# controller_board.net
KiCad netlist of a schematic drawn in EAGLE
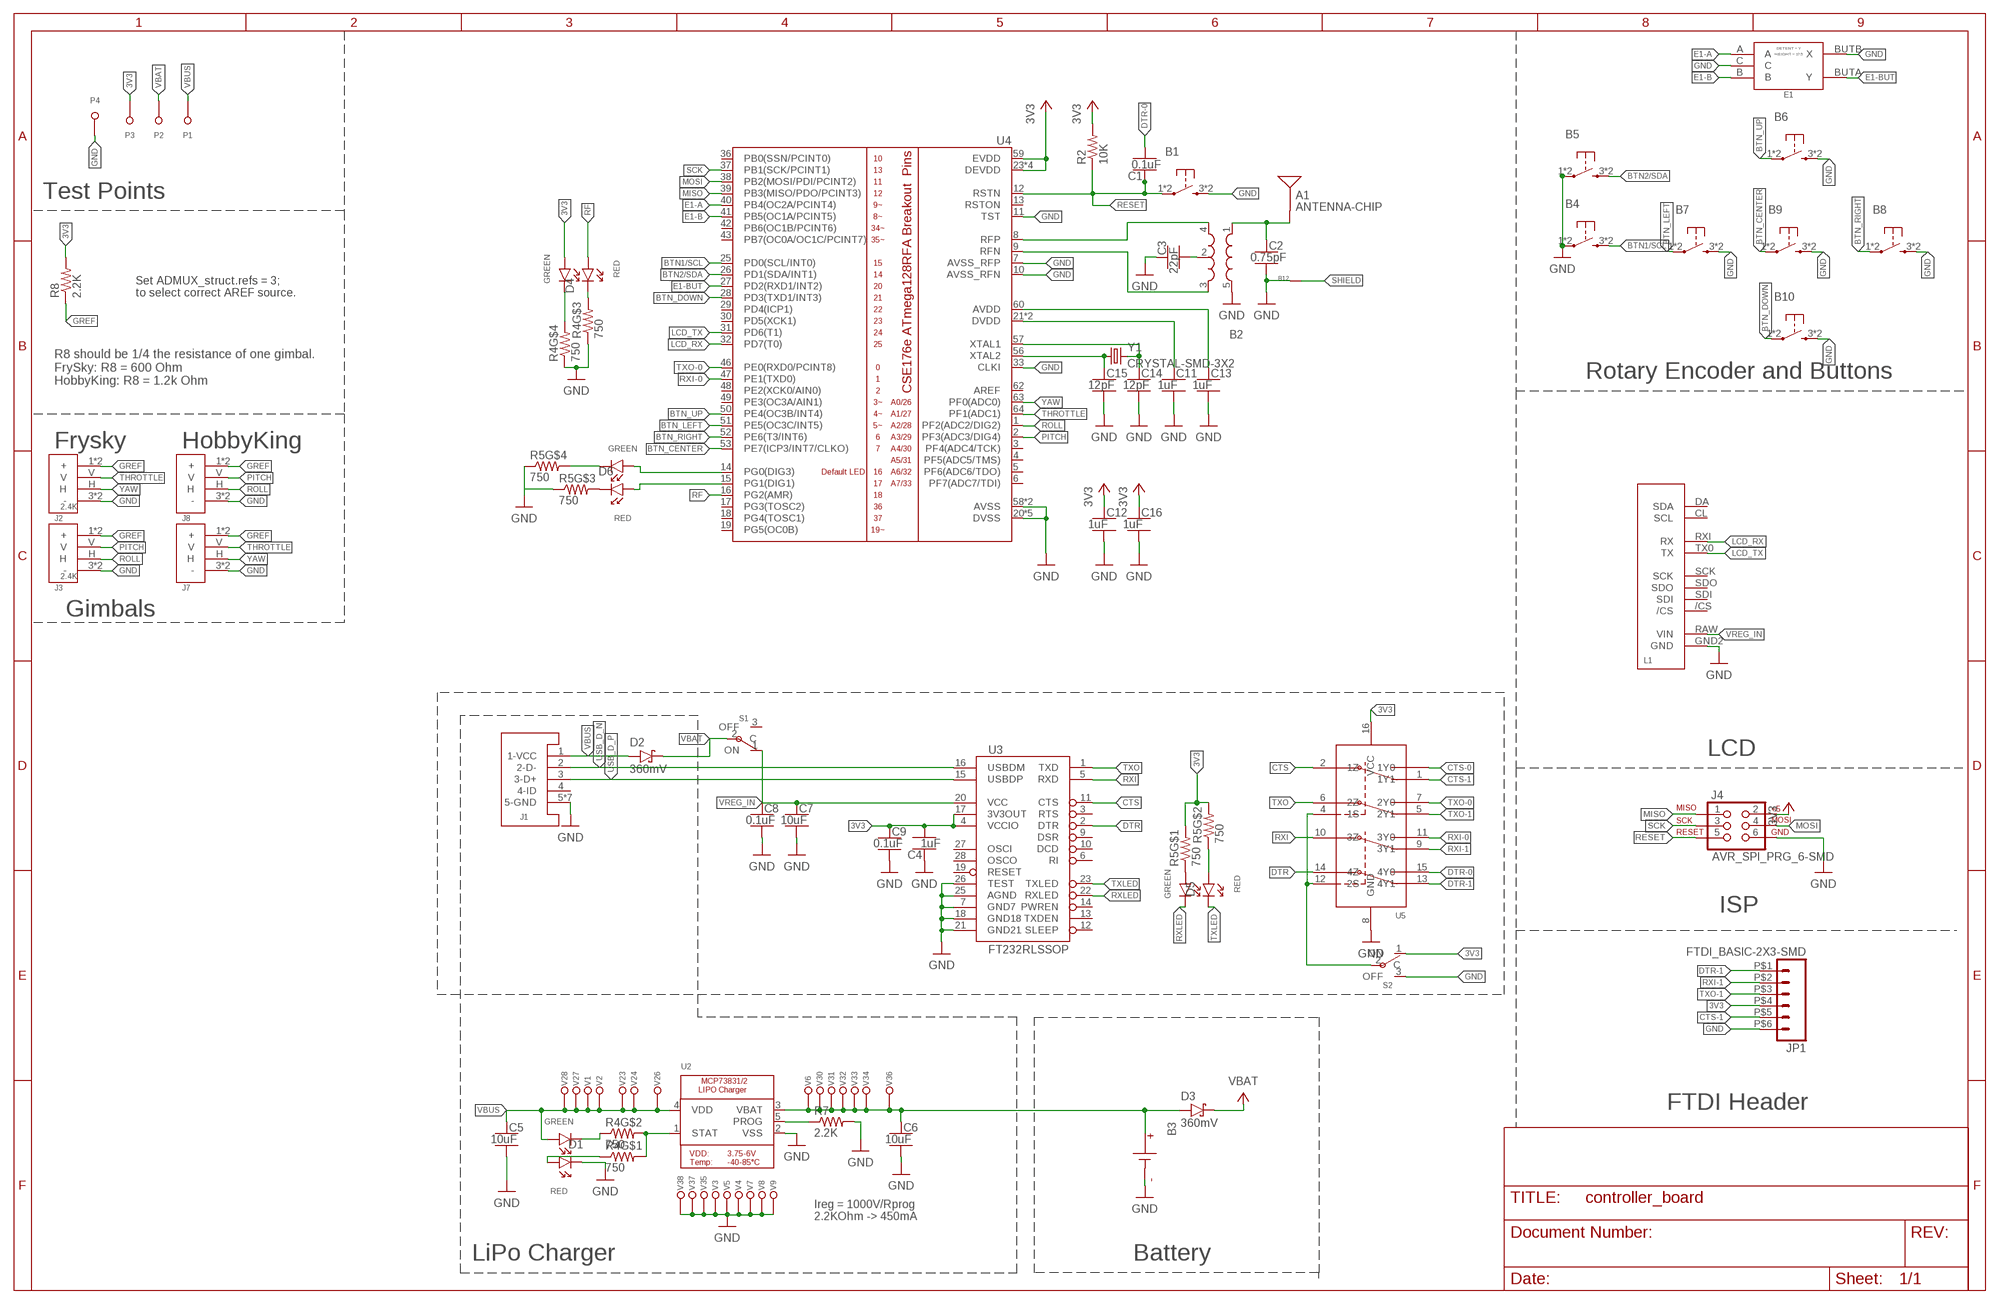
[diagram p0: schematic, sheet 1]

(export (version "E")
  (design (tool "Eeschema 10.0.6"))
  (components
    (comp (ref "A1")
      (value "ANTENNA-CHIP")
      (footprint "eagle-import:ANTENNA-CHIP")
      (fields
        (field (name "MFR") "Linx Technologies Inc.")
        (field (name "MPN") "ANT-2.45-CHP-T")
        (field (name "CREATOR") "Swanson")
        (field (name "REVIEWER") "Swanson")
      )
      (libsource (lib "eagle-import") (part "ANTENNA-CHIP"))
    )
    (comp (ref "B1")
      (value "PUSHBUTTON_-4.5X4.5")
      (footprint "eagle-import:4.5MM_TACTILE_SWITCH_TL3305AF160QG")
      (fields (field (name "CREATOR") "Swanson"))
      (libsource (lib "eagle-import") (part "PUSHBUTTON_-4.5X4.5"))
    )
    (comp (ref "B2")
      (value "BALUN0805")
      (footprint "eagle-import:BALUN")
      (fields
        (field (name "MFR") "Wurth Electronics Inc")
        (field (name "MPN") "748421245")
        (field (name "CREATOR") "Swanson")
        (field (name "REVIEWER") "Swanson")
      )
      (libsource (lib "eagle-import") (part "BALUN0805"))
    )
    (comp (ref "B3")
      (value "BATTERY-SMD")
      (footprint "eagle-import:MOLEX-BATTERY-CONNECTOR-SMD-51005-2P")
      (libsource (lib "eagle-import") (part "BATTERY-SMD"))
    )
    (comp (ref "B4")
      (value "PUSHBUTTON_-4.5X4.5")
      (footprint "eagle-import:4.5MM_TACTILE_SWITCH_TL3305AF160QG")
      (fields (field (name "CREATOR") "Swanson"))
      (libsource (lib "eagle-import") (part "PUSHBUTTON_-4.5X4.5"))
    )
    (comp (ref "B5")
      (value "PUSHBUTTON_-4.5X4.5")
      (footprint "eagle-import:4.5MM_TACTILE_SWITCH_TL3305AF160QG")
      (fields (field (name "CREATOR") "Swanson"))
      (libsource (lib "eagle-import") (part "PUSHBUTTON_-4.5X4.5"))
    )
    (comp (ref "B6")
      (value "PUSHBUTTON_-4.5X4.5")
      (footprint "eagle-import:4.5MM_TACTILE_SWITCH_TL3305AF160QG")
      (fields (field (name "CREATOR") "Swanson"))
      (libsource (lib "eagle-import") (part "PUSHBUTTON_-4.5X4.5"))
    )
    (comp (ref "B7")
      (value "PUSHBUTTON_-4.5X4.5")
      (footprint "eagle-import:4.5MM_TACTILE_SWITCH_TL3305AF160QG")
      (fields (field (name "CREATOR") "Swanson"))
      (libsource (lib "eagle-import") (part "PUSHBUTTON_-4.5X4.5"))
    )
    (comp (ref "B8")
      (value "PUSHBUTTON_-4.5X4.5")
      (footprint "eagle-import:4.5MM_TACTILE_SWITCH_TL3305AF160QG")
      (fields (field (name "CREATOR") "Swanson"))
      (libsource (lib "eagle-import") (part "PUSHBUTTON_-4.5X4.5"))
    )
    (comp (ref "B9")
      (value "PUSHBUTTON_-4.5X4.5")
      (footprint "eagle-import:4.5MM_TACTILE_SWITCH_TL3305AF160QG")
      (fields (field (name "CREATOR") "Swanson"))
      (libsource (lib "eagle-import") (part "PUSHBUTTON_-4.5X4.5"))
    )
    (comp (ref "B10")
      (value "PUSHBUTTON_-4.5X4.5")
      (footprint "eagle-import:4.5MM_TACTILE_SWITCH_TL3305AF160QG")
      (fields (field (name "CREATOR") "Swanson"))
      (libsource (lib "eagle-import") (part "PUSHBUTTON_-4.5X4.5"))
    )
    (comp (ref "B12")
      (value "NET_BRIDGE")
      (footprint "eagle-import:NET_BRIDGE")
      (fields (field (name "CREATOR") "Michael Gonzalez"))
      (libsource (lib "eagle-import") (part "NET_BRIDGE"))
    )
    (comp (ref "C1")
      (value "0.1uF")
      (footprint "eagle-import:CAPC1608X100")
      (fields (field (name "CREATOR") "Swanson"))
      (libsource (lib "eagle-import") (part "CAPACITOR-NP_SMD-0603_CERAMIC-0.1UF"))
    )
    (comp (ref "C2")
      (value "0.75pF")
      (footprint "eagle-import:CAPC1608X100")
      (fields (field (name "CREATOR") "Swanson"))
      (libsource (lib "eagle-import") (part "CAPACITOR-NP_SMD-0603_CERAMIC-0.75PF"))
    )
    (comp (ref "C3")
      (value "22pF")
      (footprint "eagle-import:CAPC1608X100")
      (fields (field (name "CREATOR") "Swanson"))
      (libsource (lib "eagle-import") (part "CAPACITOR-NP_SMD-0603_CERAMIC-22PF"))
    )
    (comp (ref "C4")
      (value "1uF")
      (footprint "eagle-import:CAPC1608X100")
      (fields (field (name "CREATOR") "Swanson"))
      (libsource (lib "eagle-import") (part "CAPACITOR-NP_SMD-0603_CERAMIC-1UF"))
    )
    (comp (ref "C5")
      (value "10uF")
      (footprint "eagle-import:CAPC1608X100")
      (fields (field (name "CREATOR") "Swanson"))
      (libsource (lib "eagle-import") (part "CAPACITOR-NP_SMD-0603_CERAMIC-10UF"))
    )
    (comp (ref "C6")
      (value "10uF")
      (footprint "eagle-import:CAPC1608X100")
      (fields (field (name "CREATOR") "Swanson"))
      (libsource (lib "eagle-import") (part "CAPACITOR-NP_SMD-0603_CERAMIC-10UF"))
    )
    (comp (ref "C7")
      (value "10uF")
      (footprint "eagle-import:CAPC1608X100")
      (fields (field (name "CREATOR") "Swanson"))
      (libsource (lib "eagle-import") (part "CAPACITOR-NP_SMD-0603_CERAMIC-10UF"))
    )
    (comp (ref "C8")
      (value "0.1uF")
      (footprint "eagle-import:CAPC1608X100")
      (fields (field (name "CREATOR") "Swanson"))
      (libsource (lib "eagle-import") (part "CAPACITOR-NP_SMD-0603_CERAMIC-0.1UF"))
    )
    (comp (ref "C9")
      (value "0.1uF")
      (footprint "eagle-import:CAPC1608X100")
      (fields (field (name "CREATOR") "Swanson"))
      (libsource (lib "eagle-import") (part "CAPACITOR-NP_SMD-0603_CERAMIC-0.1UF"))
    )
    (comp (ref "C11")
      (value "1uF")
      (footprint "eagle-import:CAPC1608X100")
      (fields (field (name "CREATOR") "Swanson"))
      (libsource (lib "eagle-import") (part "CAPACITOR-NP_SMD-0603_CERAMIC-1UF"))
    )
    (comp (ref "C12")
      (value "1uF")
      (footprint "eagle-import:CAPC1608X100")
      (fields (field (name "CREATOR") "Swanson"))
      (libsource (lib "eagle-import") (part "CAPACITOR-NP_SMD-0603_CERAMIC-1UF"))
    )
    (comp (ref "C13")
      (value "1uF")
      (footprint "eagle-import:CAPC1608X100")
      (fields (field (name "CREATOR") "Swanson"))
      (libsource (lib "eagle-import") (part "CAPACITOR-NP_SMD-0603_CERAMIC-1UF"))
    )
    (comp (ref "C14")
      (value "12pF")
      (footprint "eagle-import:CAPC1608X100")
      (fields (field (name "CREATOR") "Swanson"))
      (libsource (lib "eagle-import") (part "CAPACITOR-NP_SMD-0603_CERAMIC-12PF"))
    )
    (comp (ref "C15")
      (value "12pF")
      (footprint "eagle-import:CAPC1608X100")
      (fields (field (name "CREATOR") "Swanson"))
      (libsource (lib "eagle-import") (part "CAPACITOR-NP_SMD-0603_CERAMIC-12PF"))
    )
    (comp (ref "C16")
      (value "1uF")
      (footprint "eagle-import:CAPC1608X100")
      (fields (field (name "CREATOR") "Swanson"))
      (libsource (lib "eagle-import") (part "CAPACITOR-NP_SMD-0603_CERAMIC-1UF"))
    )
    (comp (ref "D1")
      (value "LED-2X-GREEN/RED-1.6X1.5MM")
      (footprint "eagle-import:LED-2X-LITE-ON-1.6MMX1.5MM")
      (fields
        (field (name "COLOR2") "RED")
        (field (name "COLOR1") "GREEN")
        (field (name "CREATOR") "Swanson")
      )
      (libsource (lib "eagle-import") (part "LED-2X-GREEN/RED-1.6X1.5MM"))
    )
    (comp (ref "D2")
      (value "360mV")
      (footprint "eagle-import:SOD3716X135_HS")
      (fields
        (field (name "MFR") "Toshiba Semiconductor and Storage")
        (field (name "MPN") "CRS08(TE85L,Q,M)")
        (field (name "CREATOR") "Swanson")
        (field (name "REVIEWER") "Swanson")
      )
      (libsource (lib "eagle-import") (part "DIODE-SCHOTTKY_SMD-SOD123-360MV"))
    )
    (comp (ref "D3")
      (value "360mV")
      (footprint "eagle-import:SOD3716X135_HS")
      (fields
        (field (name "MFR") "Toshiba Semiconductor and Storage")
        (field (name "MPN") "CRS08(TE85L,Q,M)")
        (field (name "CREATOR") "Swanson")
        (field (name "REVIEWER") "Swanson")
      )
      (libsource (lib "eagle-import") (part "DIODE-SCHOTTKY_SMD-SOD123-360MV"))
    )
    (comp (ref "D4")
      (value "LED-2X-GREEN/RED-1.6X1.5MM")
      (footprint "eagle-import:LED-2X-LITE-ON-1.6MMX1.5MM")
      (fields
        (field (name "COLOR2") "RED")
        (field (name "COLOR1") "GREEN")
        (field (name "CREATOR") "Swanson")
      )
      (libsource (lib "eagle-import") (part "LED-2X-GREEN/RED-1.6X1.5MM"))
    )
    (comp (ref "D5")
      (value "LED-2X-GREEN/RED-1.6X1.5MM")
      (footprint "eagle-import:LED-2X-LITE-ON-1.6MMX1.5MM")
      (fields
        (field (name "COLOR2") "RED")
        (field (name "COLOR1") "GREEN")
        (field (name "CREATOR") "Swanson")
      )
      (libsource (lib "eagle-import") (part "LED-2X-GREEN/RED-1.6X1.5MM"))
    )
    (comp (ref "D6")
      (value "LED-2X-GREEN/RED-1.6X1.5MM")
      (footprint "eagle-import:LED-2X-LITE-ON-1.6MMX1.5MM")
      (fields
        (field (name "COLOR2") "RED")
        (field (name "COLOR1") "GREEN")
        (field (name "CREATOR") "Swanson")
      )
      (libsource (lib "eagle-import") (part "LED-2X-GREEN/RED-1.6X1.5MM"))
    )
    (comp (ref "E1")
      (value "ROTARY-ENCODER-W/BUTTON-BOURNS-PEC12R-4217F")
      (footprint "eagle-import:BOURNS-PEC12R")
      (fields (field (name "DETENT") "Y") (field (name "HEIGHT") "17.5") (field (name "CREATOR") "Swanson"))
      (libsource (lib "eagle-import") (part "ROTARY-ENCODER-W/BUTTON-BOURNS-PEC12R-4217F"))
    )
    (comp (ref "J1")
      (value "USB-MICROA-AMPHENOL-10118192-0001LF")
      (footprint "eagle-import:USB-MICROA-10118192-0001LF")
      (fields (field (name "CREATOR") "Swanson"))
      (libsource (lib "eagle-import") (part "USB-MICROA-AMPHENOL-10118192-0001LF"))
    )
    (comp (ref "J2")
      (value "2.4K")
      (footprint "eagle-import:JST-13-PTH")
      (fields (field (name "CREATOR") "Swanson"))
      (libsource (lib "eagle-import") (part "FRSKY-GIMBAL-FRYSKY"))
    )
    (comp (ref "J3")
      (value "2.4K")
      (footprint "eagle-import:JST-13-PTH")
      (fields (field (name "SPICEPREFIX") "E") (field (name "CREATOR") "Swanson"))
      (libsource (lib "eagle-import") (part "FRSKY-GIMBAL-FRYSKY"))
    )
    (comp (ref "J4")
      (value "AVR_SPI_PRG_6-SMD")
      (footprint "eagle-import:2X3-SMD")
      (fields (field (name "CREATOR") "Swanson"))
      (libsource (lib "eagle-import") (part "AVR_SPI_PRG_6-SMD"))
    )
    (comp (ref "J7")
      (value "FRSKY-GIMBAL-2X-SERVO-SMD")
      (footprint "eagle-import:2X-SERVO-SMD")
      (libsource (lib "eagle-import") (part "FRSKY-GIMBAL-2X-SERVO-SMD"))
    )
    (comp (ref "J8")
      (value "FRSKY-GIMBAL-2X-SERVO-SMD")
      (footprint "eagle-import:2X-SERVO-SMD")
      (libsource (lib "eagle-import") (part "FRSKY-GIMBAL-2X-SERVO-SMD"))
    )
    (comp (ref "JP1")
      (value "FTDI_BASIC-2X3-SMD")
      (footprint "eagle-import:FTDI-2X3-SMD")
      (libsource (lib "eagle-import") (part "FTDI_BASIC-2X3-SMD"))
    )
    (comp (ref "L1")
      (value "SPARKFUN_SERLCD_SERIAL_REDUCED-SMD")
      (footprint "eagle-import:SPARKFUN_SERLCD_16X2_REDUCED_SMD")
      (fields (field (name "CREATOR") "Swanson"))
      (libsource (lib "eagle-import") (part "SPARKFUN_SERLCD_SERIAL_REDUCED-SMD"))
    )
    (comp (ref "P1")
      (value "TEST-POINT")
      (footprint "eagle-import:TEST-POINT-KEYSTONE-5000")
      (fields (field (name "CREATOR") "Swanson"))
      (libsource (lib "eagle-import") (part "TEST-POINT"))
    )
    (comp (ref "P2")
      (value "TEST-POINT")
      (footprint "eagle-import:TEST-POINT-KEYSTONE-5000")
      (fields (field (name "CREATOR") "Swanson"))
      (libsource (lib "eagle-import") (part "TEST-POINT"))
    )
    (comp (ref "P3")
      (value "TEST-POINT")
      (footprint "eagle-import:TEST-POINT-KEYSTONE-5000")
      (fields (field (name "CREATOR") "Swanson"))
      (libsource (lib "eagle-import") (part "TEST-POINT"))
    )
    (comp (ref "P4")
      (value "TEST-POINT")
      (footprint "eagle-import:TEST-POINT-KEYSTONE-5000")
      (fields (field (name "CREATOR") "Swanson"))
      (libsource (lib "eagle-import") (part "TEST-POINT"))
    )
    (comp (ref "R2")
      (value "10K")
      (footprint "eagle-import:RESC1608X55")
      (fields (field (name "CREATOR") "Swanson"))
      (libsource (lib "eagle-import") (part "RESISTOR_SMD-0603-10K"))
    )
    (comp (ref "R4")
      (value "750")
      (footprint "eagle-import:RESCAXS50P200X100X45-8")
      (fields (field (name "CREATOR") "Swanson"))
      (libsource (lib "eagle-import") (part "RESISTOR-PACK-4X-750"))
    )
    (comp (ref "R5")
      (value "750")
      (footprint "eagle-import:RESCAXS50P200X100X45-8")
      (fields (field (name "CREATOR") "Swanson"))
      (libsource (lib "eagle-import") (part "RESISTOR-PACK-4X-750"))
    )
    (comp (ref "R7")
      (value "2.2K")
      (footprint "eagle-import:RESC1608X55")
      (fields (field (name "CREATOR") "Swanson"))
      (libsource (lib "eagle-import") (part "RESISTOR_SMD-0603-2.2K"))
    )
    (comp (ref "R8")
      (value "2.2K")
      (footprint "eagle-import:RESC1608X55")
      (fields (field (name "CREATOR") "Swanson"))
      (libsource (lib "eagle-import") (part "RESISTOR_SMD-0603-2.2K"))
    )
    (comp (ref "S1")
      (value "POWER-SWITCH-MFS201N-9-Z-SMD-VERTICAL")
      (footprint "eagle-import:JS102011JCQN")
      (fields (field (name "CREATOR") "Swanson"))
      (libsource (lib "eagle-import") (part "POWER-SWITCH-MFS201N-9-Z-SMD-VERTICAL"))
    )
    (comp (ref "S2")
      (value "POWER-SWITCH-MFS201N-9-Z-SMD-VERTICAL")
      (footprint "eagle-import:JS102011JCQN")
      (fields (field (name "CREATOR") "Swanson"))
      (libsource (lib "eagle-import") (part "POWER-SWITCH-MFS201N-9-Z-SMD-VERTICAL"))
    )
    (comp (ref "U2")
      (value "MCP73831T-2ACI/OT")
      (footprint "eagle-import:SOT23-5")
      (fields (field (name "CREATOR") "Adafruit"))
      (libsource (lib "eagle-import") (part "MCP73831/2"))
    )
    (comp (ref "U3")
      (value "FT232RLSSOP")
      (footprint "eagle-import:SSOP28DB")
      (fields (field (name "CREATOR") "Swanson"))
      (libsource (lib "eagle-import") (part "FT232RLSSOP"))
    )
    (comp (ref "U4")
      (value "ATMEGA128RFA1")
      (footprint "eagle-import:QFN-64")
      (fields
        (field (name "MFR") "Atmel")
        (field (name "MPN") "ATMEGA128RFA1-ZUR00")
        (field (name "CREATOR") "Swanson")
        (field (name "REVIEWER") "Swanson")
      )
      (libsource (lib "eagle-import") (part "ATMEGA128RFA1"))
    )
    (comp (ref "U5")
      (value "DPDT-X2")
      (footprint "eagle-import:SOP65P640X110-16")
      (fields (field (name "CREATOR") "Swanson"))
      (libsource (lib "eagle-import") (part "DPDT-X2"))
    )
    (comp (ref "V1")
      (value "LOCKED-VIA-0.2")
      (footprint "eagle-import:VIA-0.2MM")
      (fields (field (name "CREATOR") "Swanson"))
      (libsource (lib "eagle-import") (part "LOCKED-VIA-0.2"))
    )
    (comp (ref "V2")
      (value "LOCKED-VIA-0.2")
      (footprint "eagle-import:VIA-0.2MM")
      (fields (field (name "CREATOR") "Swanson"))
      (libsource (lib "eagle-import") (part "LOCKED-VIA-0.2"))
    )
    (comp (ref "V3")
      (value "LOCKED-VIA-0.2")
      (footprint "eagle-import:VIA-0.2MM")
      (fields (field (name "CREATOR") "Swanson"))
      (libsource (lib "eagle-import") (part "LOCKED-VIA-0.2"))
    )
    (comp (ref "V4")
      (value "LOCKED-VIA-0.2")
      (footprint "eagle-import:VIA-0.2MM")
      (fields (field (name "CREATOR") "Swanson"))
      (libsource (lib "eagle-import") (part "LOCKED-VIA-0.2"))
    )
    (comp (ref "V5")
      (value "LOCKED-VIA-0.2")
      (footprint "eagle-import:VIA-0.2MM")
      (fields (field (name "CREATOR") "Swanson"))
      (libsource (lib "eagle-import") (part "LOCKED-VIA-0.2"))
    )
    (comp (ref "V6")
      (value "LOCKED-VIA-0.2")
      (footprint "eagle-import:VIA-0.2MM")
      (fields (field (name "CREATOR") "Swanson"))
      (libsource (lib "eagle-import") (part "LOCKED-VIA-0.2"))
    )
    (comp (ref "V7")
      (value "LOCKED-VIA-0.2")
      (footprint "eagle-import:VIA-0.2MM")
      (fields (field (name "CREATOR") "Swanson"))
      (libsource (lib "eagle-import") (part "LOCKED-VIA-0.2"))
    )
    (comp (ref "V8")
      (value "LOCKED-VIA-0.2")
      (footprint "eagle-import:VIA-0.2MM")
      (fields (field (name "CREATOR") "Swanson"))
      (libsource (lib "eagle-import") (part "LOCKED-VIA-0.2"))
    )
    (comp (ref "V9")
      (value "LOCKED-VIA-0.2")
      (footprint "eagle-import:VIA-0.2MM")
      (fields (field (name "CREATOR") "Swanson"))
      (libsource (lib "eagle-import") (part "LOCKED-VIA-0.2"))
    )
    (comp (ref "V23")
      (value "LOCKED-VIA-0.2")
      (footprint "eagle-import:VIA-0.2MM")
      (fields (field (name "CREATOR") "Swanson"))
      (libsource (lib "eagle-import") (part "LOCKED-VIA-0.2"))
    )
    (comp (ref "V24")
      (value "LOCKED-VIA-0.2")
      (footprint "eagle-import:VIA-0.2MM")
      (fields (field (name "CREATOR") "Swanson"))
      (libsource (lib "eagle-import") (part "LOCKED-VIA-0.2"))
    )
    (comp (ref "V26")
      (value "LOCKED-VIA-0.2")
      (footprint "eagle-import:VIA-0.2MM")
      (fields (field (name "CREATOR") "Swanson"))
      (libsource (lib "eagle-import") (part "LOCKED-VIA-0.2"))
    )
    (comp (ref "V27")
      (value "LOCKED-VIA-0.2")
      (footprint "eagle-import:VIA-0.2MM")
      (fields (field (name "CREATOR") "Swanson"))
      (libsource (lib "eagle-import") (part "LOCKED-VIA-0.2"))
    )
    (comp (ref "V28")
      (value "LOCKED-VIA-0.2")
      (footprint "eagle-import:VIA-0.2MM")
      (fields (field (name "CREATOR") "Swanson"))
      (libsource (lib "eagle-import") (part "LOCKED-VIA-0.2"))
    )
    (comp (ref "V30")
      (value "LOCKED-VIA-0.2")
      (footprint "eagle-import:VIA-0.2MM")
      (fields (field (name "CREATOR") "Swanson"))
      (libsource (lib "eagle-import") (part "LOCKED-VIA-0.2"))
    )
    (comp (ref "V31")
      (value "LOCKED-VIA-0.2")
      (footprint "eagle-import:VIA-0.2MM")
      (fields (field (name "CREATOR") "Swanson"))
      (libsource (lib "eagle-import") (part "LOCKED-VIA-0.2"))
    )
    (comp (ref "V32")
      (value "LOCKED-VIA-0.2")
      (footprint "eagle-import:VIA-0.2MM")
      (fields (field (name "CREATOR") "Swanson"))
      (libsource (lib "eagle-import") (part "LOCKED-VIA-0.2"))
    )
    (comp (ref "V33")
      (value "LOCKED-VIA-0.2")
      (footprint "eagle-import:VIA-0.2MM")
      (fields (field (name "CREATOR") "Swanson"))
      (libsource (lib "eagle-import") (part "LOCKED-VIA-0.2"))
    )
    (comp (ref "V34")
      (value "LOCKED-VIA-0.2")
      (footprint "eagle-import:VIA-0.2MM")
      (fields (field (name "CREATOR") "Swanson"))
      (libsource (lib "eagle-import") (part "LOCKED-VIA-0.2"))
    )
    (comp (ref "V35")
      (value "LOCKED-VIA-0.2")
      (footprint "eagle-import:VIA-0.2MM")
      (fields (field (name "CREATOR") "Swanson"))
      (libsource (lib "eagle-import") (part "LOCKED-VIA-0.2"))
    )
    (comp (ref "V36")
      (value "LOCKED-VIA-0.2")
      (footprint "eagle-import:VIA-0.2MM")
      (fields (field (name "CREATOR") "Swanson"))
      (libsource (lib "eagle-import") (part "LOCKED-VIA-0.2"))
    )
    (comp (ref "V37")
      (value "LOCKED-VIA-0.2")
      (footprint "eagle-import:VIA-0.2MM")
      (fields (field (name "CREATOR") "Swanson"))
      (libsource (lib "eagle-import") (part "LOCKED-VIA-0.2"))
    )
    (comp (ref "V38")
      (value "LOCKED-VIA-0.2")
      (footprint "eagle-import:VIA-0.2MM")
      (fields (field (name "CREATOR") "Swanson"))
      (libsource (lib "eagle-import") (part "LOCKED-VIA-0.2"))
    )
    (comp (ref "Y1")
      (value "CRYSTAL-SMD-3X2")
      (footprint "eagle-import:OSCCC320X250X85")
      (fields (field (name "CREATOR") "Swanson"))
      (libsource (lib "eagle-import") (part "CRYSTAL-SMD-3X2"))
    )
  )
  (nets
    (net (code "1") (name "3V3") (class "Default")
      (node (ref "C12") (pin "1") (pinfunction "1_1") (pintype "passive"))
      (node (ref "C16") (pin "1") (pinfunction "1_1") (pintype "passive"))
      (node (ref "C4") (pin "2") (pinfunction "2_2") (pintype "passive"))
      (node (ref "C9") (pin "1") (pinfunction "1_1") (pintype "passive"))
      (node (ref "D4") (pin "A2") (pinfunction "A2_A2") (pintype "passive"))
      (node (ref "J4") (pin "2") (pinfunction "2_2") (pintype "passive"))
      (node (ref "JP1") (pin "P$4") (pinfunction "4_P$4") (pintype "passive"))
      (node (ref "P3") (pin "T") (pinfunction "T_T") (pintype "bidirectional"))
      (node (ref "R2") (pin "2") (pinfunction "2_2") (pintype "passive"))
      (node (ref "R5") (pin "5") (pinfunction "2_5") (pintype "passive"))
      (node (ref "R5") (pin "6") (pinfunction "2_6") (pintype "passive"))
      (node (ref "R8") (pin "2") (pinfunction "2_2") (pintype "passive"))
      (node (ref "S2") (pin "1") (pinfunction "ON_1") (pintype "bidirectional"))
      (node (ref "U3") (pin "17") (pinfunction "3V3OUT_17") (pintype "output"))
      (node (ref "U3") (pin "4") (pinfunction "VCCIO_4") (pintype "power_in"))
      (node (ref "U4") (pin "23") (pinfunction "DEVDD_23") (pintype "bidirectional"))
      (node (ref "U4") (pin "34") (pinfunction "DEVDD_34") (pintype "bidirectional"))
      (node (ref "U4") (pin "44") (pinfunction "DEVDD_44") (pintype "bidirectional"))
      (node (ref "U4") (pin "54") (pinfunction "DEVDD_54") (pintype "bidirectional"))
      (node (ref "U4") (pin "59") (pinfunction "EVDD_59") (pintype "bidirectional"))
      (node (ref "U5") (pin "16") (pinfunction "VCC_16") (pintype "bidirectional"))
    )
    (net (code "2") (name "BTN1{slash}SCL") (class "Default")
      (node (ref "B4") (pin "3") (pinfunction "2_3") (pintype "passive"))
      (node (ref "B4") (pin "4") (pinfunction "2_4") (pintype "passive"))
      (node (ref "U4") (pin "25") (pinfunction "PD0(SCL/INT0)_25") (pintype "bidirectional"))
    )
    (net (code "3") (name "BTN2{slash}SDA") (class "Default")
      (node (ref "B5") (pin "3") (pinfunction "2_3") (pintype "passive"))
      (node (ref "B5") (pin "4") (pinfunction "2_4") (pintype "passive"))
      (node (ref "U4") (pin "26") (pinfunction "PD1(SDA/INT1)_26") (pintype "bidirectional"))
    )
    (net (code "4") (name "BTN_CENTER") (class "Default")
      (node (ref "B9") (pin "1") (pinfunction "1_1") (pintype "passive"))
      (node (ref "B9") (pin "2") (pinfunction "1_2") (pintype "passive"))
      (node (ref "U4") (pin "53") (pinfunction "PE7(ICP3/INT7/CLKO)_53") (pintype "bidirectional"))
    )
    (net (code "5") (name "BTN_DOWN") (class "Default")
      (node (ref "B10") (pin "1") (pinfunction "1_1") (pintype "passive"))
      (node (ref "B10") (pin "2") (pinfunction "1_2") (pintype "passive"))
      (node (ref "U4") (pin "28") (pinfunction "PD3(TXD1/INT3)_28") (pintype "bidirectional"))
    )
    (net (code "6") (name "BTN_LEFT") (class "Default")
      (node (ref "B7") (pin "1") (pinfunction "1_1") (pintype "passive"))
      (node (ref "B7") (pin "2") (pinfunction "1_2") (pintype "passive"))
      (node (ref "U4") (pin "51") (pinfunction "PE5(OC3C/INT5)_51") (pintype "bidirectional"))
    )
    (net (code "7") (name "BTN_RIGHT") (class "Default")
      (node (ref "B8") (pin "1") (pinfunction "1_1") (pintype "passive"))
      (node (ref "B8") (pin "2") (pinfunction "1_2") (pintype "passive"))
      (node (ref "U4") (pin "52") (pinfunction "PE6(T3/INT6)_52") (pintype "bidirectional"))
    )
    (net (code "8") (name "BTN_UP") (class "Default")
      (node (ref "B6") (pin "1") (pinfunction "1_1") (pintype "passive"))
      (node (ref "B6") (pin "2") (pinfunction "1_2") (pintype "passive"))
      (node (ref "U4") (pin "50") (pinfunction "PE4(OC3B/INT4)_50") (pintype "bidirectional"))
    )
    (net (code "9") (name "CTS") (class "Default")
      (node (ref "U3") (pin "11") (pinfunction "CTS_11") (pintype "input"))
      (node (ref "U5") (pin "2") (pinfunction "1Z_2") (pintype "bidirectional"))
    )
    (net (code "10") (name "CTS-0") (class "Default")
      (node (ref "U5") (pin "3") (pinfunction "1Y0_3") (pintype "bidirectional"))
    )
    (net (code "11") (name "CTS-1") (class "Default")
      (node (ref "JP1") (pin "P$5") (pinfunction "5_P$5") (pintype "passive"))
      (node (ref "U5") (pin "1") (pinfunction "1Y1_1") (pintype "bidirectional"))
    )
    (net (code "12") (name "DTR") (class "Default")
      (node (ref "U3") (pin "2") (pinfunction "DTR_2") (pintype "output"))
      (node (ref "U5") (pin "14") (pinfunction "4Z_14") (pintype "bidirectional"))
    )
    (net (code "13") (name "DTR-0") (class "Default")
      (node (ref "C1") (pin "2") (pinfunction "2_2") (pintype "passive"))
      (node (ref "U5") (pin "15") (pinfunction "4Y0_15") (pintype "bidirectional"))
    )
    (net (code "14") (name "DTR-1") (class "Default")
      (node (ref "JP1") (pin "P$1") (pinfunction "1_P$1") (pintype "passive"))
      (node (ref "U5") (pin "13") (pinfunction "4Y1_13") (pintype "bidirectional"))
    )
    (net (code "15") (name "E1-A") (class "Default")
      (node (ref "E1") (pin "A") (pinfunction "A_A") (pintype "bidirectional"))
      (node (ref "U4") (pin "40") (pinfunction "PB4(OC2A/PCINT4)_40") (pintype "bidirectional"))
    )
    (net (code "16") (name "E1-B") (class "Default")
      (node (ref "E1") (pin "B") (pinfunction "B_B") (pintype "bidirectional"))
      (node (ref "U4") (pin "41") (pinfunction "PB5(OC1A/PCINT5)_41") (pintype "bidirectional"))
    )
    (net (code "17") (name "E1-BUT") (class "Default")
      (node (ref "E1") (pin "BUTA") (pinfunction "Y_BUTA") (pintype "bidirectional"))
      (node (ref "U4") (pin "27") (pinfunction "PD2(RXD1/INT2)_27") (pintype "bidirectional"))
    )
    (net (code "18") (name "GND") (class "Default")
      (node (ref "B1") (pin "3") (pinfunction "2_3") (pintype "passive"))
      (node (ref "B1") (pin "4") (pinfunction "2_4") (pintype "passive"))
      (node (ref "B10") (pin "3") (pinfunction "2_3") (pintype "passive"))
      (node (ref "B10") (pin "4") (pinfunction "2_4") (pintype "passive"))
      (node (ref "B12") (pin "P1") (pinfunction "P1_P1") (pintype "bidirectional"))
      (node (ref "B2") (pin "5") (pinfunction "GND_5") (pintype "bidirectional"))
      (node (ref "B3") (pin "G") (pinfunction "N_G") (pintype "bidirectional"))
      (node (ref "B3") (pin "G2") (pinfunction "N_G2") (pintype "bidirectional"))
      (node (ref "B3") (pin "G3") (pinfunction "N_G3") (pintype "bidirectional"))
      (node (ref "B4") (pin "1") (pinfunction "1_1") (pintype "passive"))
      (node (ref "B4") (pin "2") (pinfunction "1_2") (pintype "passive"))
      (node (ref "B5") (pin "1") (pinfunction "1_1") (pintype "passive"))
      (node (ref "B5") (pin "2") (pinfunction "1_2") (pintype "passive"))
      (node (ref "B6") (pin "3") (pinfunction "2_3") (pintype "passive"))
      (node (ref "B6") (pin "4") (pinfunction "2_4") (pintype "passive"))
      (node (ref "B7") (pin "3") (pinfunction "2_3") (pintype "passive"))
      (node (ref "B7") (pin "4") (pinfunction "2_4") (pintype "passive"))
      (node (ref "B8") (pin "3") (pinfunction "2_3") (pintype "passive"))
      (node (ref "B8") (pin "4") (pinfunction "2_4") (pintype "passive"))
      (node (ref "B9") (pin "3") (pinfunction "2_3") (pintype "passive"))
      (node (ref "B9") (pin "4") (pinfunction "2_4") (pintype "passive"))
      (node (ref "C11") (pin "2") (pinfunction "2_2") (pintype "passive"))
      (node (ref "C12") (pin "2") (pinfunction "2_2") (pintype "passive"))
      (node (ref "C13") (pin "2") (pinfunction "2_2") (pintype "passive"))
      (node (ref "C14") (pin "2") (pinfunction "2_2") (pintype "passive"))
      (node (ref "C15") (pin "2") (pinfunction "2_2") (pintype "passive"))
      (node (ref "C16") (pin "2") (pinfunction "2_2") (pintype "passive"))
      (node (ref "C2") (pin "2") (pinfunction "2_2") (pintype "passive"))
      (node (ref "C3") (pin "1") (pinfunction "1_1") (pintype "passive"))
      (node (ref "C4") (pin "1") (pinfunction "1_1") (pintype "passive"))
      (node (ref "C5") (pin "2") (pinfunction "2_2") (pintype "passive"))
      (node (ref "C6") (pin "2") (pinfunction "2_2") (pintype "passive"))
      (node (ref "C7") (pin "2") (pinfunction "2_2") (pintype "passive"))
      (node (ref "C8") (pin "2") (pinfunction "2_2") (pintype "passive"))
      (node (ref "C9") (pin "2") (pinfunction "2_2") (pintype "passive"))
      (node (ref "D1") (pin "C1") (pinfunction "C1_C1") (pintype "passive"))
      (node (ref "E1") (pin "BUTB") (pinfunction "X_BUTB") (pintype "bidirectional"))
      (node (ref "E1") (pin "C") (pinfunction "C_C") (pintype "bidirectional"))
      (node (ref "J1") (pin "10") (pinfunction "5-GND_10") (pintype "bidirectional"))
      (node (ref "J1") (pin "11") (pinfunction "5-GND_11") (pintype "bidirectional"))
      (node (ref "J1") (pin "5") (pinfunction "5-GND_5") (pintype "bidirectional"))
      (node (ref "J1") (pin "6") (pinfunction "5-GND_6") (pintype "bidirectional"))
      (node (ref "J1") (pin "7") (pinfunction "5-GND_7") (pintype "bidirectional"))
      (node (ref "J1") (pin "8") (pinfunction "5-GND_8") (pintype "bidirectional"))
      (node (ref "J1") (pin "9") (pinfunction "5-GND_9") (pintype "bidirectional"))
      (node (ref "J2") (pin "3") (pinfunction "-_3") (pintype "bidirectional"))
      (node (ref "J2") (pin "6") (pinfunction "-_6") (pintype "bidirectional"))
      (node (ref "J3") (pin "3") (pinfunction "-_3") (pintype "bidirectional"))
      (node (ref "J3") (pin "6") (pinfunction "-_6") (pintype "bidirectional"))
      (node (ref "J4") (pin "6") (pinfunction "6_6") (pintype "passive"))
      (node (ref "J7") (pin "3") (pinfunction "-_3") (pintype "bidirectional"))
      (node (ref "J7") (pin "6") (pinfunction "-_6") (pintype "bidirectional"))
      (node (ref "J8") (pin "3") (pinfunction "-_3") (pintype "bidirectional"))
      (node (ref "J8") (pin "6") (pinfunction "-_6") (pintype "bidirectional"))
      (node (ref "JP1") (pin "P$6") (pinfunction "6_P$6") (pintype "passive"))
      (node (ref "L1") (pin "GND2") (pinfunction "GND_GND2") (pintype "bidirectional"))
      (node (ref "P4") (pin "T") (pinfunction "T_T") (pintype "bidirectional"))
      (node (ref "R4") (pin "1") (pinfunction "1_1") (pintype "passive"))
      (node (ref "R4") (pin "2") (pinfunction "1_2") (pintype "passive"))
      (node (ref "R5") (pin "1") (pinfunction "1_1") (pintype "passive"))
      (node (ref "R5") (pin "2") (pinfunction "1_2") (pintype "passive"))
      (node (ref "R7") (pin "2") (pinfunction "2_2") (pintype "passive"))
      (node (ref "S2") (pin "3") (pinfunction "OFF_3") (pintype "bidirectional"))
      (node (ref "U2") (pin "2") (pinfunction "VSS_2") (pintype "power_in"))
      (node (ref "U3") (pin "18") (pinfunction "GND18_18") (pintype "power_in"))
      (node (ref "U3") (pin "21") (pinfunction "GND21_21") (pintype "power_in"))
      (node (ref "U3") (pin "25") (pinfunction "AGND_25") (pintype "power_in"))
      (node (ref "U3") (pin "26") (pinfunction "TEST_26") (pintype "input"))
      (node (ref "U3") (pin "7") (pinfunction "GND7_7") (pintype "power_in"))
      (node (ref "U4") (pin "10") (pinfunction "AVSS_RFN_10") (pintype "bidirectional"))
      (node (ref "U4") (pin "11") (pinfunction "TST_11") (pintype "bidirectional"))
      (node (ref "U4") (pin "20") (pinfunction "DVSS_20") (pintype "bidirectional"))
      (node (ref "U4") (pin "24") (pinfunction "DVSS_24") (pintype "bidirectional"))
      (node (ref "U4") (pin "33") (pinfunction "CLKI_33") (pintype "bidirectional"))
      (node (ref "U4") (pin "35") (pinfunction "DVSS_35") (pintype "bidirectional"))
      (node (ref "U4") (pin "45") (pinfunction "DVSS_45") (pintype "bidirectional"))
      (node (ref "U4") (pin "55") (pinfunction "DVSS_55") (pintype "bidirectional"))
      (node (ref "U4") (pin "58") (pinfunction "AVSS_58") (pintype "bidirectional"))
      (node (ref "U4") (pin "61") (pinfunction "AVSS_61") (pintype "bidirectional"))
      (node (ref "U4") (pin "7") (pinfunction "AVSS_RFP_7") (pintype "bidirectional"))
      (node (ref "U5") (pin "8") (pinfunction "GND_8") (pintype "bidirectional"))
      (node (ref "V3") (pin "P1") (pinfunction "N_P1") (pintype "bidirectional"))
      (node (ref "V35") (pin "P1") (pinfunction "N_P1") (pintype "bidirectional"))
      (node (ref "V37") (pin "P1") (pinfunction "N_P1") (pintype "bidirectional"))
      (node (ref "V38") (pin "P1") (pinfunction "N_P1") (pintype "bidirectional"))
      (node (ref "V4") (pin "P1") (pinfunction "N_P1") (pintype "bidirectional"))
      (node (ref "V5") (pin "P1") (pinfunction "N_P1") (pintype "bidirectional"))
      (node (ref "V7") (pin "P1") (pinfunction "N_P1") (pintype "bidirectional"))
      (node (ref "V8") (pin "P1") (pinfunction "N_P1") (pintype "bidirectional"))
      (node (ref "V9") (pin "P1") (pinfunction "N_P1") (pintype "bidirectional"))
    )
    (net (code "19") (name "GREF") (class "Default")
      (node (ref "J2") (pin "1") (pinfunction "+_1") (pintype "bidirectional"))
      (node (ref "J2") (pin "4") (pinfunction "+_4") (pintype "bidirectional"))
      (node (ref "J3") (pin "1") (pinfunction "+_1") (pintype "bidirectional"))
      (node (ref "J3") (pin "4") (pinfunction "+_4") (pintype "bidirectional"))
      (node (ref "J7") (pin "1") (pinfunction "+_1") (pintype "bidirectional"))
      (node (ref "J7") (pin "4") (pinfunction "+_4") (pintype "bidirectional"))
      (node (ref "J8") (pin "1") (pinfunction "+_1") (pintype "bidirectional"))
      (node (ref "J8") (pin "4") (pinfunction "+_4") (pintype "bidirectional"))
      (node (ref "R8") (pin "1") (pinfunction "1_1") (pintype "passive"))
    )
    (net (code "20") (name "LCD_RX") (class "Default")
      (node (ref "L1") (pin "RXI") (pinfunction "RX_RXI") (pintype "bidirectional"))
      (node (ref "U4") (pin "32") (pinfunction "PD7(T0)_32") (pintype "bidirectional"))
    )
    (net (code "21") (name "LCD_TX") (class "Default")
      (node (ref "L1") (pin "TX0") (pinfunction "TX_TX0") (pintype "bidirectional"))
      (node (ref "U4") (pin "31") (pinfunction "PD6(T1)_31") (pintype "bidirectional"))
    )
    (net (code "22") (name "MISO") (class "Default")
      (node (ref "J4") (pin "1") (pinfunction "1_1") (pintype "passive"))
      (node (ref "U4") (pin "39") (pinfunction "PB3(MISO/PDO/PCINT3)_39") (pintype "bidirectional"))
    )
    (net (code "23") (name "MOSI") (class "Default")
      (node (ref "J4") (pin "4") (pinfunction "4_4") (pintype "passive"))
      (node (ref "U4") (pin "38") (pinfunction "PB2(MOSI/PDI/PCINT2)_38") (pintype "bidirectional"))
    )
    (net (code "24") (name "Net-(A1-SIGNAL)") (class "Default")
      (node (ref "A1") (pin "FEED") (pinfunction "SIGNAL_FEED") (pintype "bidirectional"))
      (node (ref "B2") (pin "1") (pinfunction "IN_1") (pintype "bidirectional"))
      (node (ref "C2") (pin "1") (pinfunction "1_1") (pintype "passive"))
    )
    (net (code "25") (name "Net-(B2-GND-Pad2)") (class "Default")
      (node (ref "B2") (pin "2") (pinfunction "GND_2") (pintype "bidirectional"))
      (node (ref "C3") (pin "2") (pinfunction "2_2") (pintype "passive"))
    )
    (net (code "26") (name "Net-(B2-OUT1)") (class "Default")
      (node (ref "B2") (pin "4") (pinfunction "OUT1_4") (pintype "bidirectional"))
      (node (ref "U4") (pin "8") (pinfunction "RFP_8") (pintype "bidirectional"))
    )
    (net (code "27") (name "Net-(B2-OUT2)") (class "Default")
      (node (ref "B2") (pin "3") (pinfunction "OUT2_3") (pintype "bidirectional"))
      (node (ref "U4") (pin "9") (pinfunction "RFN_9") (pintype "bidirectional"))
    )
    (net (code "28") (name "Net-(C11-Pad1)") (class "Default")
      (node (ref "C11") (pin "1") (pinfunction "1_1") (pintype "passive"))
      (node (ref "U4") (pin "21") (pinfunction "DVDD_21") (pintype "bidirectional"))
      (node (ref "U4") (pin "22") (pinfunction "DVDD_22") (pintype "bidirectional"))
    )
    (net (code "29") (name "Net-(R4A-1)") (class "Default")
      (node (ref "D1") (pin "A1") (pinfunction "A1_A1") (pintype "passive"))
      (node (ref "R4") (pin "4") (pinfunction "1_4") (pintype "passive"))
    )
    (net (code "30") (name "Net-(R4A-2)") (class "Default")
      (node (ref "R4") (pin "5") (pinfunction "2_5") (pintype "passive"))
      (node (ref "R4") (pin "6") (pinfunction "2_6") (pintype "passive"))
      (node (ref "U2") (pin "1") (pinfunction "STAT_1") (pintype "output"))
    )
    (net (code "31") (name "Net-(R4B-1)") (class "Default")
      (node (ref "D1") (pin "C2") (pinfunction "C2_C2") (pintype "passive"))
      (node (ref "R4") (pin "3") (pinfunction "1_3") (pintype "passive"))
    )
    (net (code "32") (name "Net-(R4C-2)") (class "Default")
      (node (ref "D4") (pin "C1") (pinfunction "C1_C1") (pintype "passive"))
      (node (ref "R4") (pin "7") (pinfunction "2_7") (pintype "passive"))
    )
    (net (code "33") (name "Net-(R4D-2)") (class "Default")
      (node (ref "D4") (pin "C2") (pinfunction "C2_C2") (pintype "passive"))
      (node (ref "R4") (pin "8") (pinfunction "2_8") (pintype "passive"))
    )
    (net (code "34") (name "Net-(R5A-1)") (class "Default")
      (node (ref "D5") (pin "A2") (pinfunction "A2_A2") (pintype "passive"))
      (node (ref "R5") (pin "4") (pinfunction "1_4") (pintype "passive"))
    )
    (net (code "35") (name "Net-(R5B-1)") (class "Default")
      (node (ref "D5") (pin "A1") (pinfunction "A1_A1") (pintype "passive"))
      (node (ref "R5") (pin "3") (pinfunction "1_3") (pintype "passive"))
    )
    (net (code "36") (name "Net-(R5C-2)") (class "Default")
      (node (ref "D6") (pin "C1") (pinfunction "C1_C1") (pintype "passive"))
      (node (ref "R5") (pin "7") (pinfunction "2_7") (pintype "passive"))
    )
    (net (code "37") (name "Net-(R5D-2)") (class "Default")
      (node (ref "D6") (pin "C2") (pinfunction "C2_C2") (pintype "passive"))
      (node (ref "R5") (pin "8") (pinfunction "2_8") (pintype "passive"))
    )
    (net (code "38") (name "Net-(S2-C)") (class "Default")
      (node (ref "S2") (pin "2") (pinfunction "C_2") (pintype "bidirectional"))
      (node (ref "U5") (pin "12") (pinfunction "2S_12") (pintype "bidirectional"))
      (node (ref "U5") (pin "4") (pinfunction "1S_4") (pintype "bidirectional"))
    )
    (net (code "39") (name "Net-(U2-PROG)") (class "Default")
      (node (ref "R7") (pin "1") (pinfunction "1_1") (pintype "passive"))
      (node (ref "U2") (pin "5") (pinfunction "PROG_5") (pintype "input"))
    )
    (net (code "40") (name "Net-(U2-VBAT)") (class "Default")
      (node (ref "B3") (pin "P") (pinfunction "P_P") (pintype "bidirectional"))
      (node (ref "C6") (pin "1") (pinfunction "1_1") (pintype "passive"))
      (node (ref "D3") (pin "A") (pinfunction "A_A") (pintype "passive"))
      (node (ref "U2") (pin "3") (pinfunction "VBAT_3") (pintype "power_in"))
      (node (ref "V30") (pin "P1") (pinfunction "N_P1") (pintype "bidirectional"))
      (node (ref "V31") (pin "P1") (pinfunction "N_P1") (pintype "bidirectional"))
      (node (ref "V32") (pin "P1") (pinfunction "N_P1") (pintype "bidirectional"))
      (node (ref "V33") (pin "P1") (pinfunction "N_P1") (pintype "bidirectional"))
      (node (ref "V34") (pin "P1") (pinfunction "N_P1") (pintype "bidirectional"))
      (node (ref "V36") (pin "P1") (pinfunction "N_P1") (pintype "bidirectional"))
      (node (ref "V6") (pin "P1") (pinfunction "N_P1") (pintype "bidirectional"))
    )
    (net (code "41") (name "Net-(U4-AVDD)") (class "Default")
      (node (ref "C13") (pin "1") (pinfunction "1_1") (pintype "passive"))
      (node (ref "U4") (pin "60") (pinfunction "AVDD_60") (pintype "bidirectional"))
    )
    (net (code "42") (name "Net-(U4-PG0(DIG3))") (class "Default")
      (node (ref "D6") (pin "A2") (pinfunction "A2_A2") (pintype "passive"))
      (node (ref "U4") (pin "14") (pinfunction "PG0(DIG3)_14") (pintype "bidirectional"))
    )
    (net (code "43") (name "Net-(U4-PG1(DIG1))") (class "Default")
      (node (ref "D6") (pin "A1") (pinfunction "A1_A1") (pintype "passive"))
      (node (ref "U4") (pin "15") (pinfunction "PG1(DIG1)_15") (pintype "bidirectional"))
    )
    (net (code "44") (name "Net-(U4-XTAL1)") (class "Default")
      (node (ref "C14") (pin "1") (pinfunction "1_1") (pintype "passive"))
      (node (ref "U4") (pin "57") (pinfunction "XTAL1_57") (pintype "bidirectional"))
      (node (ref "Y1") (pin "3") (pinfunction "2_3") (pintype "passive"))
    )
    (net (code "45") (name "Net-(U4-XTAL2)") (class "Default")
      (node (ref "C15") (pin "1") (pinfunction "1_1") (pintype "passive"))
      (node (ref "U4") (pin "56") (pinfunction "XTAL2_56") (pintype "bidirectional"))
      (node (ref "Y1") (pin "1") (pinfunction "1_1") (pintype "passive"))
    )
    (net (code "46") (name "PITCH") (class "Default")
      (node (ref "J3") (pin "V") (pinfunction "V_V") (pintype "bidirectional"))
      (node (ref "J8") (pin "V") (pinfunction "V_V") (pintype "bidirectional"))
      (node (ref "U4") (pin "2") (pinfunction "PF3(ADC3/DIG4)_2") (pintype "bidirectional"))
    )
    (net (code "47") (name "RESET") (class "Default")
      (node (ref "B1") (pin "1") (pinfunction "1_1") (pintype "passive"))
      (node (ref "B1") (pin "2") (pinfunction "1_2") (pintype "passive"))
      (node (ref "C1") (pin "1") (pinfunction "1_1") (pintype "passive"))
      (node (ref "J4") (pin "5") (pinfunction "5_5") (pintype "passive"))
      (node (ref "R2") (pin "1") (pinfunction "1_1") (pintype "passive"))
      (node (ref "U4") (pin "12") (pinfunction "RSTN_12") (pintype "bidirectional"))
    )
    (net (code "48") (name "RF") (class "Default")
      (node (ref "D4") (pin "A1") (pinfunction "A1_A1") (pintype "passive"))
      (node (ref "U4") (pin "16") (pinfunction "PG2(AMR)_16") (pintype "bidirectional"))
    )
    (net (code "49") (name "ROLL") (class "Default")
      (node (ref "J3") (pin "H") (pinfunction "H_H") (pintype "bidirectional"))
      (node (ref "J8") (pin "H") (pinfunction "H_H") (pintype "bidirectional"))
      (node (ref "U4") (pin "1") (pinfunction "PF2(ADC2/DIG2)_1") (pintype "bidirectional"))
    )
    (net (code "50") (name "RXI") (class "Default")
      (node (ref "U3") (pin "5") (pinfunction "RXD_5") (pintype "input"))
      (node (ref "U5") (pin "10") (pinfunction "3Z_10") (pintype "bidirectional"))
    )
    (net (code "51") (name "RXI-0") (class "Default")
      (node (ref "U4") (pin "47") (pinfunction "PE1(TXD0)_47") (pintype "bidirectional"))
      (node (ref "U5") (pin "11") (pinfunction "3Y0_11") (pintype "bidirectional"))
    )
    (net (code "52") (name "RXI-1") (class "Default")
      (node (ref "JP1") (pin "P$2") (pinfunction "2_P$2") (pintype "passive"))
      (node (ref "U5") (pin "9") (pinfunction "3Y1_9") (pintype "bidirectional"))
    )
    (net (code "53") (name "RXLED") (class "Default")
      (node (ref "D5") (pin "C2") (pinfunction "C2_C2") (pintype "passive"))
      (node (ref "U3") (pin "22") (pinfunction "RXLED_22") (pintype "input"))
    )
    (net (code "54") (name "SCK") (class "Default")
      (node (ref "J4") (pin "3") (pinfunction "3_3") (pintype "passive"))
      (node (ref "U4") (pin "37") (pinfunction "PB1(SCK/PCINT1)_37") (pintype "bidirectional"))
    )
    (net (code "55") (name "SHIELD") (class "Default")
      (node (ref "B12") (pin "P2") (pinfunction "P2_P2") (pintype "bidirectional"))
    )
    (net (code "56") (name "THROTTLE") (class "Default")
      (node (ref "J2") (pin "V") (pinfunction "V_V") (pintype "bidirectional"))
      (node (ref "J7") (pin "V") (pinfunction "V_V") (pintype "bidirectional"))
      (node (ref "U4") (pin "64") (pinfunction "PF1(ADC1)_64") (pintype "bidirectional"))
    )
    (net (code "57") (name "TXLED") (class "Default")
      (node (ref "D5") (pin "C1") (pinfunction "C1_C1") (pintype "passive"))
      (node (ref "U3") (pin "23") (pinfunction "TXLED_23") (pintype "input"))
    )
    (net (code "58") (name "TXO") (class "Default")
      (node (ref "U3") (pin "1") (pinfunction "TXD_1") (pintype "output"))
      (node (ref "U5") (pin "6") (pinfunction "2Z_6") (pintype "bidirectional"))
    )
    (net (code "59") (name "TXO-0") (class "Default")
      (node (ref "U4") (pin "46") (pinfunction "PE0(RXD0/PCINT8)_46") (pintype "bidirectional"))
      (node (ref "U5") (pin "7") (pinfunction "2Y0_7") (pintype "bidirectional"))
    )
    (net (code "60") (name "TXO-1") (class "Default")
      (node (ref "JP1") (pin "P$3") (pinfunction "3_P$3") (pintype "passive"))
      (node (ref "U5") (pin "5") (pinfunction "2Y1_5") (pintype "bidirectional"))
    )
    (net (code "61") (name "USB_D_N") (class "Default")
      (node (ref "J1") (pin "2") (pinfunction "2-D-_2") (pintype "bidirectional"))
      (node (ref "U3") (pin "16") (pinfunction "USBDM_16") (pintype "bidirectional"))
    )
    (net (code "62") (name "USB_D_P") (class "Default")
      (node (ref "J1") (pin "3") (pinfunction "3-D+_3") (pintype "bidirectional"))
      (node (ref "U3") (pin "15") (pinfunction "USBDP_15") (pintype "bidirectional"))
    )
    (net (code "63") (name "VBAT") (class "Default")
      (node (ref "D2") (pin "C") (pinfunction "C_C") (pintype "passive"))
      (node (ref "D3") (pin "C") (pinfunction "C_C") (pintype "passive"))
      (node (ref "P2") (pin "T") (pinfunction "T_T") (pintype "bidirectional"))
      (node (ref "S1") (pin "2") (pinfunction "C_2") (pintype "bidirectional"))
    )
    (net (code "64") (name "VBUS") (class "Default")
      (node (ref "C5") (pin "1") (pinfunction "1_1") (pintype "passive"))
      (node (ref "D1") (pin "A2") (pinfunction "A2_A2") (pintype "passive"))
      (node (ref "D2") (pin "A") (pinfunction "A_A") (pintype "passive"))
      (node (ref "J1") (pin "1") (pinfunction "1-VCC_1") (pintype "bidirectional"))
      (node (ref "P1") (pin "T") (pinfunction "T_T") (pintype "bidirectional"))
      (node (ref "U2") (pin "4") (pinfunction "VDD_4") (pintype "power_in"))
      (node (ref "V1") (pin "P1") (pinfunction "N_P1") (pintype "bidirectional"))
      (node (ref "V2") (pin "P1") (pinfunction "N_P1") (pintype "bidirectional"))
      (node (ref "V23") (pin "P1") (pinfunction "N_P1") (pintype "bidirectional"))
      (node (ref "V24") (pin "P1") (pinfunction "N_P1") (pintype "bidirectional"))
      (node (ref "V26") (pin "P1") (pinfunction "N_P1") (pintype "bidirectional"))
      (node (ref "V27") (pin "P1") (pinfunction "N_P1") (pintype "bidirectional"))
      (node (ref "V28") (pin "P1") (pinfunction "N_P1") (pintype "bidirectional"))
    )
    (net (code "65") (name "VREG_IN") (class "Default")
      (node (ref "C7") (pin "1") (pinfunction "1_1") (pintype "passive"))
      (node (ref "C8") (pin "1") (pinfunction "1_1") (pintype "passive"))
      (node (ref "L1") (pin "RAW") (pinfunction "VIN_RAW") (pintype "bidirectional"))
      (node (ref "S1") (pin "1") (pinfunction "ON_1") (pintype "bidirectional"))
      (node (ref "U3") (pin "20") (pinfunction "VCC_20") (pintype "power_in"))
    )
    (net (code "66") (name "YAW") (class "Default")
      (node (ref "J2") (pin "H") (pinfunction "H_H") (pintype "bidirectional"))
      (node (ref "J7") (pin "H") (pinfunction "H_H") (pintype "bidirectional"))
      (node (ref "U4") (pin "63") (pinfunction "PF0(ADC0)_63") (pintype "bidirectional"))
    )
    (net (code "67") (name "unconnected-(J1-4-ID-Pad4)") (class "Default")
      (node (ref "J1") (pin "4") (pinfunction "4-ID_4") (pintype "bidirectional"))
    )
    (net (code "68") (name "unconnected-(L1-PadSCK)") (class "Default")
      (node (ref "L1") (pin "SCK") (pinfunction "SCK_SCK") (pintype "bidirectional"))
    )
    (net (code "69") (name "unconnected-(L1-PadSDI)") (class "Default")
      (node (ref "L1") (pin "SDI") (pinfunction "SDI_SDI") (pintype "bidirectional"))
    )
    (net (code "70") (name "unconnected-(L1-PadSDO)") (class "Default")
      (node (ref "L1") (pin "SDO") (pinfunction "SDO_SDO") (pintype "bidirectional"))
    )
    (net (code "71") (name "unconnected-(L1-Pad{slash}CS)") (class "Default")
      (node (ref "L1") (pin "/CS") (pinfunction "/CS_/CS") (pintype "bidirectional"))
    )
    (net (code "72") (name "unconnected-(L1-SCL-PadCL)") (class "Default")
      (node (ref "L1") (pin "CL") (pinfunction "SCL_CL") (pintype "bidirectional"))
    )
    (net (code "73") (name "unconnected-(L1-SDA-PadDA)") (class "Default")
      (node (ref "L1") (pin "DA") (pinfunction "SDA_DA") (pintype "bidirectional"))
    )
    (net (code "74") (name "unconnected-(S1-OFF-Pad3)") (class "Default")
      (node (ref "S1") (pin "3") (pinfunction "OFF_3") (pintype "bidirectional"))
    )
    (net (code "75") (name "unconnected-(U3-DCD-Pad10)") (class "Default")
      (node (ref "U3") (pin "10") (pinfunction "DCD_10") (pintype "input"))
    )
    (net (code "76") (name "unconnected-(U3-DSR-Pad9)") (class "Default")
      (node (ref "U3") (pin "9") (pinfunction "DSR_9") (pintype "input"))
    )
    (net (code "77") (name "unconnected-(U3-OSCI-Pad27)") (class "Default")
      (node (ref "U3") (pin "27") (pinfunction "OSCI_27") (pintype "input"))
    )
    (net (code "78") (name "unconnected-(U3-OSCO-Pad28)") (class "Default")
      (node (ref "U3") (pin "28") (pinfunction "OSCO_28") (pintype "output"))
    )
    (net (code "79") (name "unconnected-(U3-PWREN-Pad14)") (class "Default")
      (node (ref "U3") (pin "14") (pinfunction "PWREN_14") (pintype "input"))
    )
    (net (code "80") (name "unconnected-(U3-RESET-Pad19)") (class "Default")
      (node (ref "U3") (pin "19") (pinfunction "RESET_19") (pintype "input"))
    )
    (net (code "81") (name "unconnected-(U3-RI-Pad6)") (class "Default")
      (node (ref "U3") (pin "6") (pinfunction "RI_6") (pintype "input"))
    )
    (net (code "82") (name "unconnected-(U3-RTS-Pad3)") (class "Default")
      (node (ref "U3") (pin "3") (pinfunction "RTS_3") (pintype "output"))
    )
    (net (code "83") (name "unconnected-(U3-SLEEP-Pad12)") (class "Default")
      (node (ref "U3") (pin "12") (pinfunction "SLEEP_12") (pintype "input"))
    )
    (net (code "84") (name "unconnected-(U3-TXDEN-Pad13)") (class "Default")
      (node (ref "U3") (pin "13") (pinfunction "TXDEN_13") (pintype "input"))
    )
    (net (code "85") (name "unconnected-(U4-AREF-Pad62)") (class "Default")
      (node (ref "U4") (pin "62") (pinfunction "AREF_62") (pintype "bidirectional"))
    )
    (net (code "86") (name "unconnected-(U4-PB0(SSN{slash}PCINT0)-Pad36)") (class "Default")
      (node (ref "U4") (pin "36") (pinfunction "PB0(SSN/PCINT0)_36") (pintype "bidirectional"))
    )
    (net (code "87") (name "unconnected-(U4-PB6(OC1B{slash}PCINT6)-Pad42)") (class "Default")
      (node (ref "U4") (pin "42") (pinfunction "PB6(OC1B/PCINT6)_42") (pintype "bidirectional"))
    )
    (net (code "88") (name "unconnected-(U4-PB7(OC0A{slash}OC1C{slash}PCINT7)-Pad43)") (class "Default")
      (node (ref "U4") (pin "43") (pinfunction "PB7(OC0A/OC1C/PCINT7)_43") (pintype "bidirectional"))
    )
    (net (code "89") (name "unconnected-(U4-PD4(ICP1)-Pad29)") (class "Default")
      (node (ref "U4") (pin "29") (pinfunction "PD4(ICP1)_29") (pintype "bidirectional"))
    )
    (net (code "90") (name "unconnected-(U4-PD5(XCK1)-Pad30)") (class "Default")
      (node (ref "U4") (pin "30") (pinfunction "PD5(XCK1)_30") (pintype "bidirectional"))
    )
    (net (code "91") (name "unconnected-(U4-PE2(XCK0{slash}AIN0)-Pad48)") (class "Default")
      (node (ref "U4") (pin "48") (pinfunction "PE2(XCK0/AIN0)_48") (pintype "bidirectional"))
    )
    (net (code "92") (name "unconnected-(U4-PE3(OC3A{slash}AIN1)-Pad49)") (class "Default")
      (node (ref "U4") (pin "49") (pinfunction "PE3(OC3A/AIN1)_49") (pintype "bidirectional"))
    )
    (net (code "93") (name "unconnected-(U4-PF4(ADC4{slash}TCK)-Pad3)") (class "Default")
      (node (ref "U4") (pin "3") (pinfunction "PF4(ADC4/TCK)_3") (pintype "bidirectional"))
    )
    (net (code "94") (name "unconnected-(U4-PF5(ADC5{slash}TMS)-Pad4)") (class "Default")
      (node (ref "U4") (pin "4") (pinfunction "PF5(ADC5/TMS)_4") (pintype "bidirectional"))
    )
    (net (code "95") (name "unconnected-(U4-PF6(ADC6{slash}TDO)-Pad5)") (class "Default")
      (node (ref "U4") (pin "5") (pinfunction "PF6(ADC6/TDO)_5") (pintype "bidirectional"))
    )
    (net (code "96") (name "unconnected-(U4-PF7(ADC7{slash}TDI)-Pad6)") (class "Default")
      (node (ref "U4") (pin "6") (pinfunction "PF7(ADC7/TDI)_6") (pintype "bidirectional"))
    )
    (net (code "97") (name "unconnected-(U4-PG3(TOSC2)-Pad17)") (class "Default")
      (node (ref "U4") (pin "17") (pinfunction "PG3(TOSC2)_17") (pintype "bidirectional"))
    )
    (net (code "98") (name "unconnected-(U4-PG4(TOSC1)-Pad18)") (class "Default")
      (node (ref "U4") (pin "18") (pinfunction "PG4(TOSC1)_18") (pintype "bidirectional"))
    )
    (net (code "99") (name "unconnected-(U4-PG5(OC0B)-Pad19)") (class "Default")
      (node (ref "U4") (pin "19") (pinfunction "PG5(OC0B)_19") (pintype "bidirectional"))
    )
    (net (code "100") (name "unconnected-(U4-RSTON-Pad13)") (class "Default")
      (node (ref "U4") (pin "13") (pinfunction "RSTON_13") (pintype "bidirectional"))
    )
  )
)
